# DRL10FPWM.net
KiCad netlist of a schematic drawn in Altium Designer
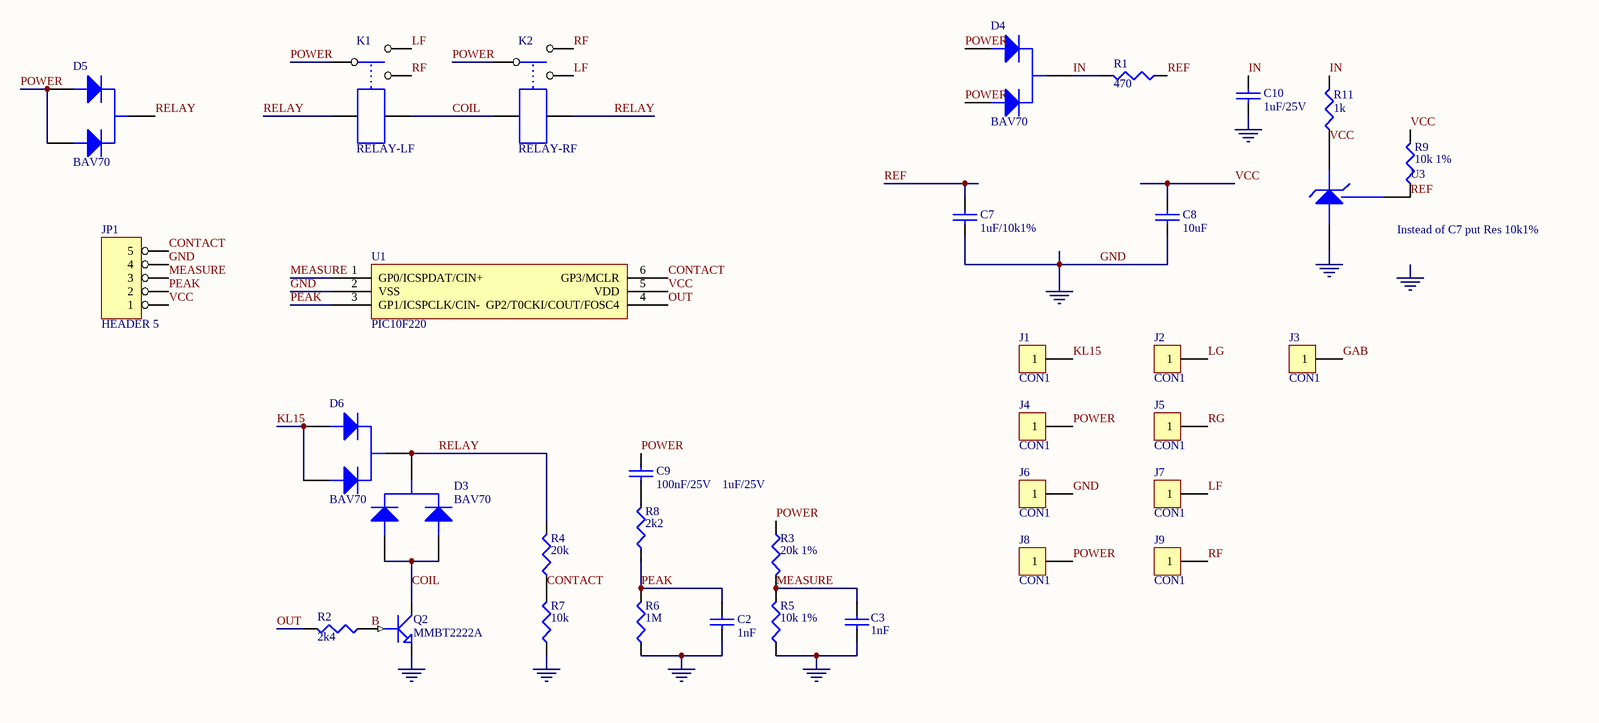
[diagram p0: DRL10FPWM.SchDoc]

(export (version "E")
  (design (tool "Eeschema 10.0.6"))
  (components
    (comp (ref "C2")
      (value "1nF")
      (footprint "0603")
      (description "Capacitor")
      (libsource (lib "*") (part "CAP"))
    )
    (comp (ref "C3")
      (value "1nF")
      (footprint "0603")
      (description "Capacitor")
      (libsource (lib "*") (part "CAP"))
    )
    (comp (ref "C7")
      (value "1uF/10k1%")
      (footprint "0805")
      (description "Capacitor")
      (libsource (lib "*") (part "CAP"))
    )
    (comp (ref "C8")
      (value "10uF")
      (footprint "0805")
      (description "Capacitor")
      (libsource (lib "*") (part "CAP"))
    )
    (comp (ref "C9")
      (value "100nF/25V")
      (footprint "0603")
      (description "Capacitor")
      (libsource (lib "*") (part "CAP"))
    )
    (comp (ref "C10")
      (value "1uF/25V")
      (footprint "0805")
      (description "Capacitor")
      (libsource (lib "*") (part "CAP"))
    )
    (comp (ref "D3")
      (value "BAV70")
      (footprint "SOT-23")
      (libsource (lib "Devices") (part "DUAL DIODE BAV70"))
    )
    (comp (ref "D4")
      (value "BAV70")
      (footprint "SOT-23")
      (libsource (lib "Devices") (part "DUAL DIODE BAV70"))
    )
    (comp (ref "D5")
      (value "BAV70")
      (footprint "SOT-23")
      (libsource (lib "Devices") (part "DUAL DIODE BAV70"))
    )
    (comp (ref "D6")
      (value "BAV70")
      (footprint "SOT-23")
      (libsource (lib "Devices") (part "DUAL DIODE BAV70"))
    )
    (comp (ref "J1")
      (value "CON1")
      (footprint "SIP1 - WIRE")
      (description "Connector")
      (libsource (lib "Miscellaneous Devices") (part "CON1"))
    )
    (comp (ref "J2")
      (value "CON1")
      (footprint "SIP1 - WIRE")
      (description "Connector")
      (libsource (lib "Miscellaneous Devices") (part "CON1"))
    )
    (comp (ref "J3")
      (value "CON1")
      (footprint "SIP1 - WIRE")
      (description "Connector")
      (libsource (lib "Miscellaneous Devices") (part "CON1"))
    )
    (comp (ref "J4")
      (value "CON1")
      (footprint "SIP1 - WIRE")
      (description "Connector")
      (libsource (lib "Miscellaneous Devices") (part "CON1"))
    )
    (comp (ref "J5")
      (value "CON1")
      (footprint "SIP1 - WIRE")
      (description "Connector")
      (libsource (lib "Miscellaneous Devices") (part "CON1"))
    )
    (comp (ref "J6")
      (value "CON1")
      (footprint "SIP1 - WIRE")
      (description "Connector")
      (libsource (lib "Miscellaneous Devices") (part "CON1"))
    )
    (comp (ref "J7")
      (value "CON1")
      (footprint "SIP1 - WIRE")
      (description "Connector")
      (libsource (lib "Miscellaneous Devices") (part "CON1"))
    )
    (comp (ref "J8")
      (value "CON1")
      (footprint "SIP1 - WIRE")
      (description "Connector")
      (libsource (lib "Miscellaneous Devices") (part "CON1"))
    )
    (comp (ref "J9")
      (value "CON1")
      (footprint "SIP1 - WIRE")
      (description "Connector")
      (libsource (lib "Miscellaneous Devices") (part "CON1"))
    )
    (comp (ref "JP1")
      (value "HEADER 5")
      (footprint "SIP5 - PGM")
      (libsource (lib "Miscellaneous Devices") (part "HEADER 5"))
    )
    (comp (ref "K1")
      (value "RELAY-LF")
      (footprint "RELAY5PIN")
      (libsource (lib "Miscellaneous Devices") (part "RELAY-SPDT"))
    )
    (comp (ref "K2")
      (value "RELAY-RF")
      (footprint "RELAY5PIN")
      (libsource (lib "Miscellaneous Devices") (part "RELAY-SPDT"))
    )
    (comp (ref "Q2")
      (value "MMBT2222A")
      (footprint "SOT-23")
      (description "NPN Transistor")
      (libsource (lib "Miscellaneous Devices") (part "NPN1"))
    )
    (comp (ref "R1") (value "470") (footprint "0603") (libsource (lib "Miscellaneous Devices") (part "RES1")))
    (comp (ref "R2") (value "2k4") (footprint "0603") (libsource (lib "Miscellaneous Devices") (part "RES1")))
    (comp (ref "R3")
      (value "20k 1%")
      (footprint "0603")
      (libsource (lib "Miscellaneous Devices") (part "RES1"))
    )
    (comp (ref "R4") (value "20k") (footprint "0603") (libsource (lib "Miscellaneous Devices") (part "RES1")))
    (comp (ref "R5")
      (value "10k 1%")
      (footprint "0603")
      (libsource (lib "Miscellaneous Devices") (part "RES1"))
    )
    (comp (ref "R6") (value "1M") (footprint "0603") (libsource (lib "Miscellaneous Devices") (part "RES1")))
    (comp (ref "R7") (value "10k") (footprint "0603") (libsource (lib "Miscellaneous Devices") (part "RES1")))
    (comp (ref "R8") (value "2k2") (footprint "0603") (libsource (lib "Miscellaneous Devices") (part "RES1")))
    (comp (ref "R9")
      (value "10k 1%")
      (footprint "0603")
      (libsource (lib "Miscellaneous Devices") (part "RES1"))
    )
    (comp (ref "R11") (value "1k") (footprint "0603") (libsource (lib "Miscellaneous Devices") (part "RES1")))
    (comp (ref "U1") (value "PIC10F220") (footprint "SOT23 - 6") (libsource (lib "MCU") (part "PIC10F206")))
    (comp (ref "U3") (value "TL431") (footprint "SOT-23") (libsource (lib "Devices") (part "TL431")))
  )
  (nets
    (net (code "1") (name "/B") (class "Default")
      (node (ref "Q2") (pin "1") (pinfunction "B_1") (pintype "input"))
      (node (ref "R2") (pin "1") (pinfunction "1_1") (pintype "passive"))
    )
    (net (code "2") (name "/COIL") (class "Default")
      (node (ref "D3") (pin "1") (pinfunction "A1_1") (pintype "passive"))
      (node (ref "D3") (pin "3") (pinfunction "A2_3") (pintype "passive"))
      (node (ref "K1") (pin "5") (pinfunction "5_5") (pintype "passive"))
      (node (ref "K2") (pin "4") (pinfunction "4_4") (pintype "passive"))
      (node (ref "Q2") (pin "2") (pinfunction "C_2") (pintype "passive"))
    )
    (net (code "3") (name "/CONTACT") (class "Default")
      (node (ref "JP1") (pin "5") (pinfunction "5_5") (pintype "passive"))
      (node (ref "R4") (pin "1") (pinfunction "1_1") (pintype "passive"))
      (node (ref "R7") (pin "2") (pinfunction "2_2") (pintype "passive"))
      (node (ref "U1") (pin "6") (pinfunction "GP3/MCLR_6") (pintype "passive"))
    )
    (net (code "4") (name "/GAB") (class "Default")
      (node (ref "J3") (pin "1") (pinfunction "1_1") (pintype "passive"))
    )
    (net (code "5") (name "/IN") (class "Default")
      (node (ref "C10") (pin "1") (pinfunction "1_1") (pintype "passive"))
      (node (ref "D4") (pin "2") (pinfunction "K_2") (pintype "passive"))
      (node (ref "R1") (pin "2") (pinfunction "2_2") (pintype "passive"))
      (node (ref "R11") (pin "2") (pinfunction "2_2") (pintype "passive"))
    )
    (net (code "6") (name "/KL15") (class "Default")
      (node (ref "D6") (pin "1") (pinfunction "A1_1") (pintype "passive"))
      (node (ref "D6") (pin "3") (pinfunction "A2_3") (pintype "passive"))
      (node (ref "J1") (pin "1") (pinfunction "1_1") (pintype "passive"))
    )
    (net (code "7") (name "/LF") (class "Default")
      (node (ref "J7") (pin "1") (pinfunction "1_1") (pintype "passive"))
      (node (ref "K1") (pin "2") (pinfunction "2_2") (pintype "passive"))
      (node (ref "K2") (pin "3") (pinfunction "3_3") (pintype "passive"))
    )
    (net (code "8") (name "/LG") (class "Default")
      (node (ref "J2") (pin "1") (pinfunction "1_1") (pintype "passive"))
    )
    (net (code "9") (name "/MEASURE") (class "Default")
      (node (ref "C3") (pin "2") (pinfunction "2_2") (pintype "passive"))
      (node (ref "JP1") (pin "3") (pinfunction "3_3") (pintype "passive"))
      (node (ref "R3") (pin "2") (pinfunction "2_2") (pintype "passive"))
      (node (ref "R5") (pin "2") (pinfunction "2_2") (pintype "passive"))
      (node (ref "U1") (pin "1") (pinfunction "GP0/ICSPDAT/CIN+_1") (pintype "passive"))
    )
    (net (code "10") (name "/OUT") (class "Default")
      (node (ref "R2") (pin "2") (pinfunction "2_2") (pintype "passive"))
      (node (ref "U1") (pin "4") (pinfunction "GP2/T0CKI/COUT/FOSC4_4") (pintype "passive"))
    )
    (net (code "11") (name "/PEAK") (class "Default")
      (node (ref "C2") (pin "1") (pinfunction "1_1") (pintype "passive"))
      (node (ref "JP1") (pin "2") (pinfunction "2_2") (pintype "passive"))
      (node (ref "R6") (pin "2") (pinfunction "2_2") (pintype "passive"))
      (node (ref "R8") (pin "1") (pinfunction "1_1") (pintype "passive"))
      (node (ref "U1") (pin "3") (pinfunction "GP1/ICSPCLK/CIN-_3") (pintype "passive"))
    )
    (net (code "12") (name "/POWER") (class "Default")
      (node (ref "C9") (pin "1") (pinfunction "1_1") (pintype "passive"))
      (node (ref "D4") (pin "1") (pinfunction "A1_1") (pintype "passive"))
      (node (ref "D4") (pin "3") (pinfunction "A2_3") (pintype "passive"))
      (node (ref "D5") (pin "1") (pinfunction "A1_1") (pintype "passive"))
      (node (ref "D5") (pin "3") (pinfunction "A2_3") (pintype "passive"))
      (node (ref "J4") (pin "1") (pinfunction "1_1") (pintype "passive"))
      (node (ref "J8") (pin "1") (pinfunction "1_1") (pintype "passive"))
      (node (ref "K1") (pin "1") (pinfunction "1_1") (pintype "passive"))
      (node (ref "K2") (pin "1") (pinfunction "1_1") (pintype "passive"))
      (node (ref "R3") (pin "1") (pinfunction "1_1") (pintype "passive"))
    )
    (net (code "13") (name "/REF") (class "Default")
      (node (ref "C7") (pin "1") (pinfunction "1_1") (pintype "passive"))
      (node (ref "R1") (pin "1") (pinfunction "1_1") (pintype "passive"))
      (node (ref "R9") (pin "1") (pinfunction "1_1") (pintype "passive"))
      (node (ref "U3") (pin "1") (pinfunction "REF_1") (pintype "passive"))
    )
    (net (code "14") (name "/RELAY") (class "Default")
      (node (ref "D3") (pin "2") (pinfunction "K_2") (pintype "passive"))
      (node (ref "D5") (pin "2") (pinfunction "K_2") (pintype "passive"))
      (node (ref "D6") (pin "2") (pinfunction "K_2") (pintype "passive"))
      (node (ref "K1") (pin "4") (pinfunction "4_4") (pintype "passive"))
      (node (ref "K2") (pin "5") (pinfunction "5_5") (pintype "passive"))
      (node (ref "R4") (pin "2") (pinfunction "2_2") (pintype "passive"))
    )
    (net (code "15") (name "/RF") (class "Default")
      (node (ref "J9") (pin "1") (pinfunction "1_1") (pintype "passive"))
      (node (ref "K1") (pin "3") (pinfunction "3_3") (pintype "passive"))
      (node (ref "K2") (pin "2") (pinfunction "2_2") (pintype "passive"))
    )
    (net (code "16") (name "/RG") (class "Default")
      (node (ref "J5") (pin "1") (pinfunction "1_1") (pintype "passive"))
    )
    (net (code "17") (name "/VCC") (class "Default")
      (node (ref "C8") (pin "1") (pinfunction "1_1") (pintype "passive"))
      (node (ref "JP1") (pin "1") (pinfunction "1_1") (pintype "passive"))
      (node (ref "R11") (pin "1") (pinfunction "1_1") (pintype "passive"))
      (node (ref "R9") (pin "2") (pinfunction "2_2") (pintype "passive"))
      (node (ref "U1") (pin "5") (pinfunction "VDD_5") (pintype "passive"))
      (node (ref "U3") (pin "3") (pinfunction "K_3") (pintype "passive"))
    )
    (net (code "18") (name "GND") (class "Default")
      (node (ref "C10") (pin "2") (pinfunction "2_2") (pintype "passive"))
      (node (ref "C2") (pin "2") (pinfunction "2_2") (pintype "passive"))
      (node (ref "C3") (pin "1") (pinfunction "1_1") (pintype "passive"))
      (node (ref "C7") (pin "2") (pinfunction "2_2") (pintype "passive"))
      (node (ref "C8") (pin "2") (pinfunction "2_2") (pintype "passive"))
      (node (ref "J6") (pin "1") (pinfunction "1_1") (pintype "passive"))
      (node (ref "JP1") (pin "4") (pinfunction "4_4") (pintype "passive"))
      (node (ref "Q2") (pin "3") (pinfunction "E_3") (pintype "passive"))
      (node (ref "R5") (pin "1") (pinfunction "1_1") (pintype "passive"))
      (node (ref "R6") (pin "1") (pinfunction "1_1") (pintype "passive"))
      (node (ref "R7") (pin "1") (pinfunction "1_1") (pintype "passive"))
      (node (ref "U1") (pin "2") (pinfunction "VSS_2") (pintype "passive"))
      (node (ref "U3") (pin "2") (pinfunction "A_2") (pintype "passive"))
    )
    (net (code "19") (name "Net-(C9-Pad2)") (class "Default")
      (node (ref "C9") (pin "2") (pinfunction "2_2") (pintype "passive"))
      (node (ref "R8") (pin "2") (pinfunction "2_2") (pintype "passive"))
    )
  )
)
